# lab.net
KiCad netlist of a schematic drawn in Altium Designer
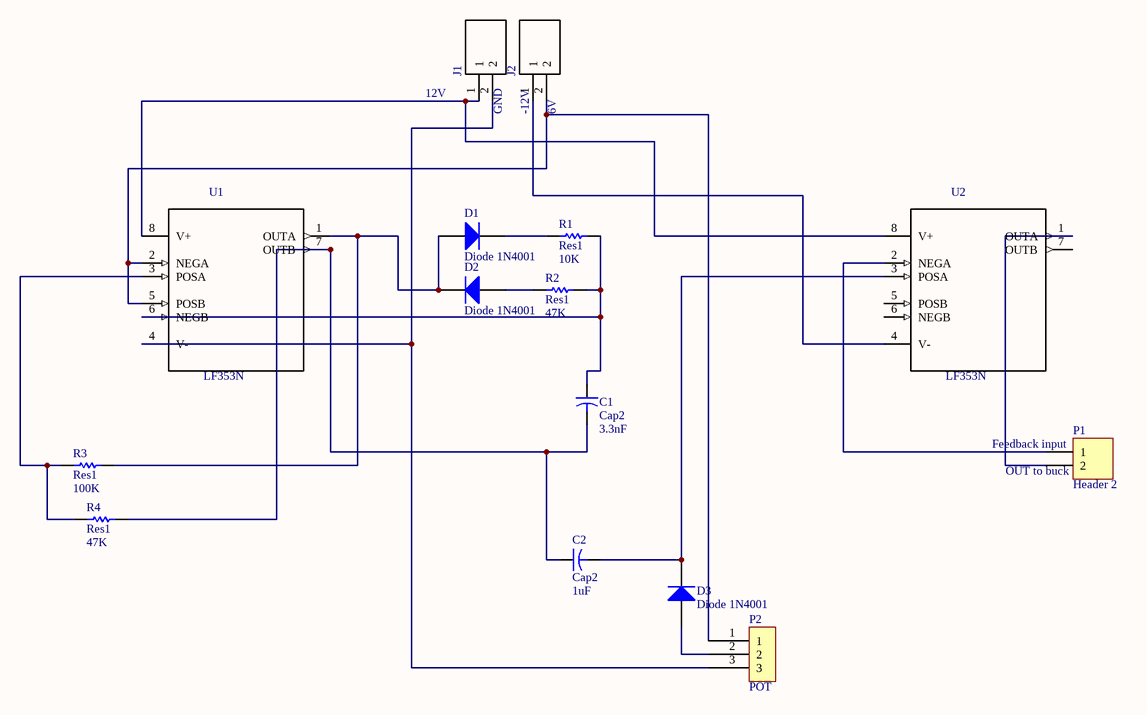
[diagram p0: lab.SchDoc]

(export (version "E")
  (design (tool "Eeschema 10.0.6"))
  (components
    (comp (ref "C1")
      (value "Cap2")
      (footprint "CAPR5-4X5")
      (description "Capacitor")
      (fields (field (name "ALTIUM_VALUE") "3.3nF") (field (name "PUBLISHER") "Altium Limited"))
      (libsource (lib "Miscellaneous Devices") (part "Cap2"))
    )
    (comp (ref "C2")
      (value "Cap2")
      (footprint "CAPR5-4X5")
      (description "Capacitor")
      (fields (field (name "ALTIUM_VALUE") "1uF") (field (name "PUBLISHER") "Altium Limited"))
      (libsource (lib "Miscellaneous Devices") (part "Cap2"))
    )
    (comp (ref "D1")
      (value "Diode 1N4001")
      (footprint "DO-41")
      (description "1 Amp General Purpose Rectifier")
      (fields (field (name "PUBLISHER") "Altium Limited"))
      (libsource (lib "Miscellaneous Devices") (part "Diode 1N4001"))
    )
    (comp (ref "D2")
      (value "Diode 1N4001")
      (footprint "DO-41")
      (description "1 Amp General Purpose Rectifier")
      (fields (field (name "PUBLISHER") "Altium Limited"))
      (libsource (lib "Miscellaneous Devices") (part "Diode 1N4001"))
    )
    (comp (ref "D3")
      (value "Diode 1N4001")
      (footprint "DO-41")
      (description "1 Amp General Purpose Rectifier")
      (fields (field (name "PUBLISHER") "Altium Limited"))
      (libsource (lib "Miscellaneous Devices") (part "Diode 1N4001"))
    )
    (comp (ref "J1")
      (value "1546215-2")
      (footprint "*TE_1546215-2")
      (description "TERMI-BLOK PCB MOUNT, 90 2P.")
      (fields (field (name "MF") "TE Connectivity"))
      (libsource (lib "1546215-2") (part "1546215-2"))
    )
    (comp (ref "J2")
      (value "1546215-2")
      (footprint "*TE_1546215-2")
      (description "TERMI-BLOK PCB MOUNT, 90 2P.")
      (fields (field (name "MF") "TE Connectivity"))
      (libsource (lib "1546215-2") (part "1546215-2"))
    )
    (comp (ref "P1")
      (value "Header 2")
      (footprint "HDR1X2")
      (description "Header, 2-Pin")
      (fields (field (name "PUBLISHER") "Altium Limited"))
      (libsource (lib "Miscellaneous Connectors") (part "Header 2"))
    )
    (comp (ref "P2")
      (value "POT")
      (footprint "POT")
      (description "JST (JAPAN SOLDERLESS TERMINALS) - B8B-XH-A (LF)(SN) - HEADER, VERTICAL, 8WAY")
      (fields
        (field (name "MANUFACTURER") "JST")
        (field (name "MANUFACTURER PART NUMBER") "B8B-XH-A(LF)(SN)")
      )
      (libsource (lib "Schlib1") (part "POT"))
    )
    (comp (ref "R1")
      (value "Res1")
      (footprint "AXIAL-0.3")
      (description "Resistor")
      (fields (field (name "ALTIUM_VALUE") "10K") (field (name "PUBLISHER") "Altium Limited"))
      (libsource (lib "Miscellaneous Devices") (part "Res1"))
    )
    (comp (ref "R2")
      (value "Res1")
      (footprint "AXIAL-0.3")
      (description "Resistor")
      (fields (field (name "ALTIUM_VALUE") "47K") (field (name "PUBLISHER") "Altium Limited"))
      (libsource (lib "Miscellaneous Devices") (part "Res1"))
    )
    (comp (ref "R3")
      (value "Res1")
      (footprint "AXIAL-0.3")
      (description "Resistor")
      (fields (field (name "ALTIUM_VALUE") "100K") (field (name "PUBLISHER") "Altium Limited"))
      (libsource (lib "Miscellaneous Devices") (part "Res1"))
    )
    (comp (ref "R4")
      (value "Res1")
      (footprint "AXIAL-0.3")
      (description "Resistor")
      (fields (field (name "ALTIUM_VALUE") "47K") (field (name "PUBLISHER") "Altium Limited"))
      (libsource (lib "Miscellaneous Devices") (part "Res1"))
    )
    (comp (ref "U1")
      (value "LF353N")
      (footprint "*DIP254P762X508-8")
      (description "8 pin Wide Bandwidth Dual JFET Input Operational Amplifier 40 per tube")
      (fields (field (name "MF") "STMicroelectronics"))
      (libsource (lib "LF353N") (part "LF353N"))
    )
    (comp (ref "U2")
      (value "LF353N")
      (footprint "*DIP254P762X508-8")
      (description "8 pin Wide Bandwidth Dual JFET Input Operational Amplifier 40 per tube")
      (fields (field (name "MF") "STMicroelectronics"))
      (libsource (lib "LF353N") (part "LF353N"))
    )
  )
  (nets
    (net (code "1") (name "Net-(D1-A)") (class "Default")
      (node (ref "D1") (pin "1") (pinfunction "A_1") (pintype "passive"))
      (node (ref "D2") (pin "2") (pinfunction "K_2") (pintype "passive"))
      (node (ref "R3") (pin "2") (pinfunction "2_2") (pintype "passive"))
      (node (ref "U1") (pin "1") (pinfunction "OUTA_1") (pintype "output"))
    )
    (net (code "2") (name "Net-(D1-K)") (class "Default")
      (node (ref "D1") (pin "2") (pinfunction "K_2") (pintype "passive"))
      (node (ref "R1") (pin "1") (pinfunction "1_1") (pintype "passive"))
    )
    (net (code "3") (name "Net-(D2-A)") (class "Default")
      (node (ref "D2") (pin "1") (pinfunction "A_1") (pintype "passive"))
      (node (ref "R2") (pin "1") (pinfunction "1_1") (pintype "passive"))
    )
    (net (code "4") (name "Net-(D3-A)") (class "Default")
      (node (ref "D3") (pin "1") (pinfunction "A_1") (pintype "passive"))
      (node (ref "P2") (pin "2") (pinfunction "2_2") (pintype "passive"))
    )
    (net (code "5") (name "Net-(D3-K)") (class "Default")
      (node (ref "C2") (pin "2") (pinfunction "2_2") (pintype "passive"))
      (node (ref "D3") (pin "2") (pinfunction "K_2") (pintype "passive"))
      (node (ref "U2") (pin "3") (pinfunction "POSA_3") (pintype "input"))
    )
    (net (code "6") (name "Net-(U1-NEGA)") (class "Default")
      (node (ref "J2") (pin "2") (pinfunction "2_2") (pintype "passive"))
      (node (ref "P2") (pin "1") (pinfunction "1_1") (pintype "passive"))
      (node (ref "U1") (pin "2") (pinfunction "NEGA_2") (pintype "input"))
      (node (ref "U1") (pin "5") (pinfunction "POSB_5") (pintype "input"))
    )
    (net (code "7") (name "Net-(U1-NEGB)") (class "Default")
      (node (ref "C1") (pin "1") (pinfunction "1_1") (pintype "passive"))
      (node (ref "R1") (pin "2") (pinfunction "2_2") (pintype "passive"))
      (node (ref "R2") (pin "2") (pinfunction "2_2") (pintype "passive"))
      (node (ref "U1") (pin "6") (pinfunction "NEGB_6") (pintype "input"))
    )
    (net (code "8") (name "Net-(U1-OUTB)") (class "Default")
      (node (ref "C1") (pin "2") (pinfunction "2_2") (pintype "passive"))
      (node (ref "C2") (pin "1") (pinfunction "1_1") (pintype "passive"))
      (node (ref "R4") (pin "2") (pinfunction "2_2") (pintype "passive"))
      (node (ref "U1") (pin "7") (pinfunction "OUTB_7") (pintype "output"))
    )
    (net (code "9") (name "Net-(U1-POSA)") (class "Default")
      (node (ref "R3") (pin "1") (pinfunction "1_1") (pintype "passive"))
      (node (ref "R4") (pin "1") (pinfunction "1_1") (pintype "passive"))
      (node (ref "U1") (pin "3") (pinfunction "POSA_3") (pintype "input"))
    )
    (net (code "10") (name "Net-(U1-V+)") (class "Default")
      (node (ref "J1") (pin "1") (pinfunction "1_1") (pintype "passive"))
      (node (ref "U1") (pin "8") (pinfunction "V+_8") (pintype "power_in"))
      (node (ref "U2") (pin "8") (pinfunction "V+_8") (pintype "power_in"))
    )
    (net (code "11") (name "Net-(U1-V-)") (class "Default")
      (node (ref "J1") (pin "2") (pinfunction "2_2") (pintype "passive"))
      (node (ref "P2") (pin "3") (pinfunction "3_3") (pintype "passive"))
      (node (ref "U1") (pin "4") (pinfunction "V-_4") (pintype "power_in"))
    )
    (net (code "12") (name "Net-(U2-NEGA)") (class "Default")
      (node (ref "P1") (pin "1") (pinfunction "1_1") (pintype "passive"))
      (node (ref "U2") (pin "2") (pinfunction "NEGA_2") (pintype "input"))
    )
    (net (code "13") (name "Net-(U2-OUTA)") (class "Default")
      (node (ref "P1") (pin "2") (pinfunction "2_2") (pintype "passive"))
      (node (ref "U2") (pin "1") (pinfunction "OUTA_1") (pintype "output"))
    )
    (net (code "14") (name "Net-(U2-V-)") (class "Default")
      (node (ref "J2") (pin "1") (pinfunction "1_1") (pintype "passive"))
      (node (ref "U2") (pin "4") (pinfunction "V-_4") (pintype "power_in"))
    )
    (net (code "15") (name "unconnected-(U2-NEGB-Pad6)") (class "Default")
      (node (ref "U2") (pin "6") (pinfunction "NEGB_6") (pintype "input"))
    )
    (net (code "16") (name "unconnected-(U2-OUTB-Pad7)") (class "Default")
      (node (ref "U2") (pin "7") (pinfunction "OUTB_7") (pintype "output"))
    )
    (net (code "17") (name "unconnected-(U2-POSB-Pad5)") (class "Default")
      (node (ref "U2") (pin "5") (pinfunction "POSB_5") (pintype "input"))
    )
  )
)
